# ES_Daisy_Pod_Rev3.net
KiCad netlist of a schematic drawn in EAGLE
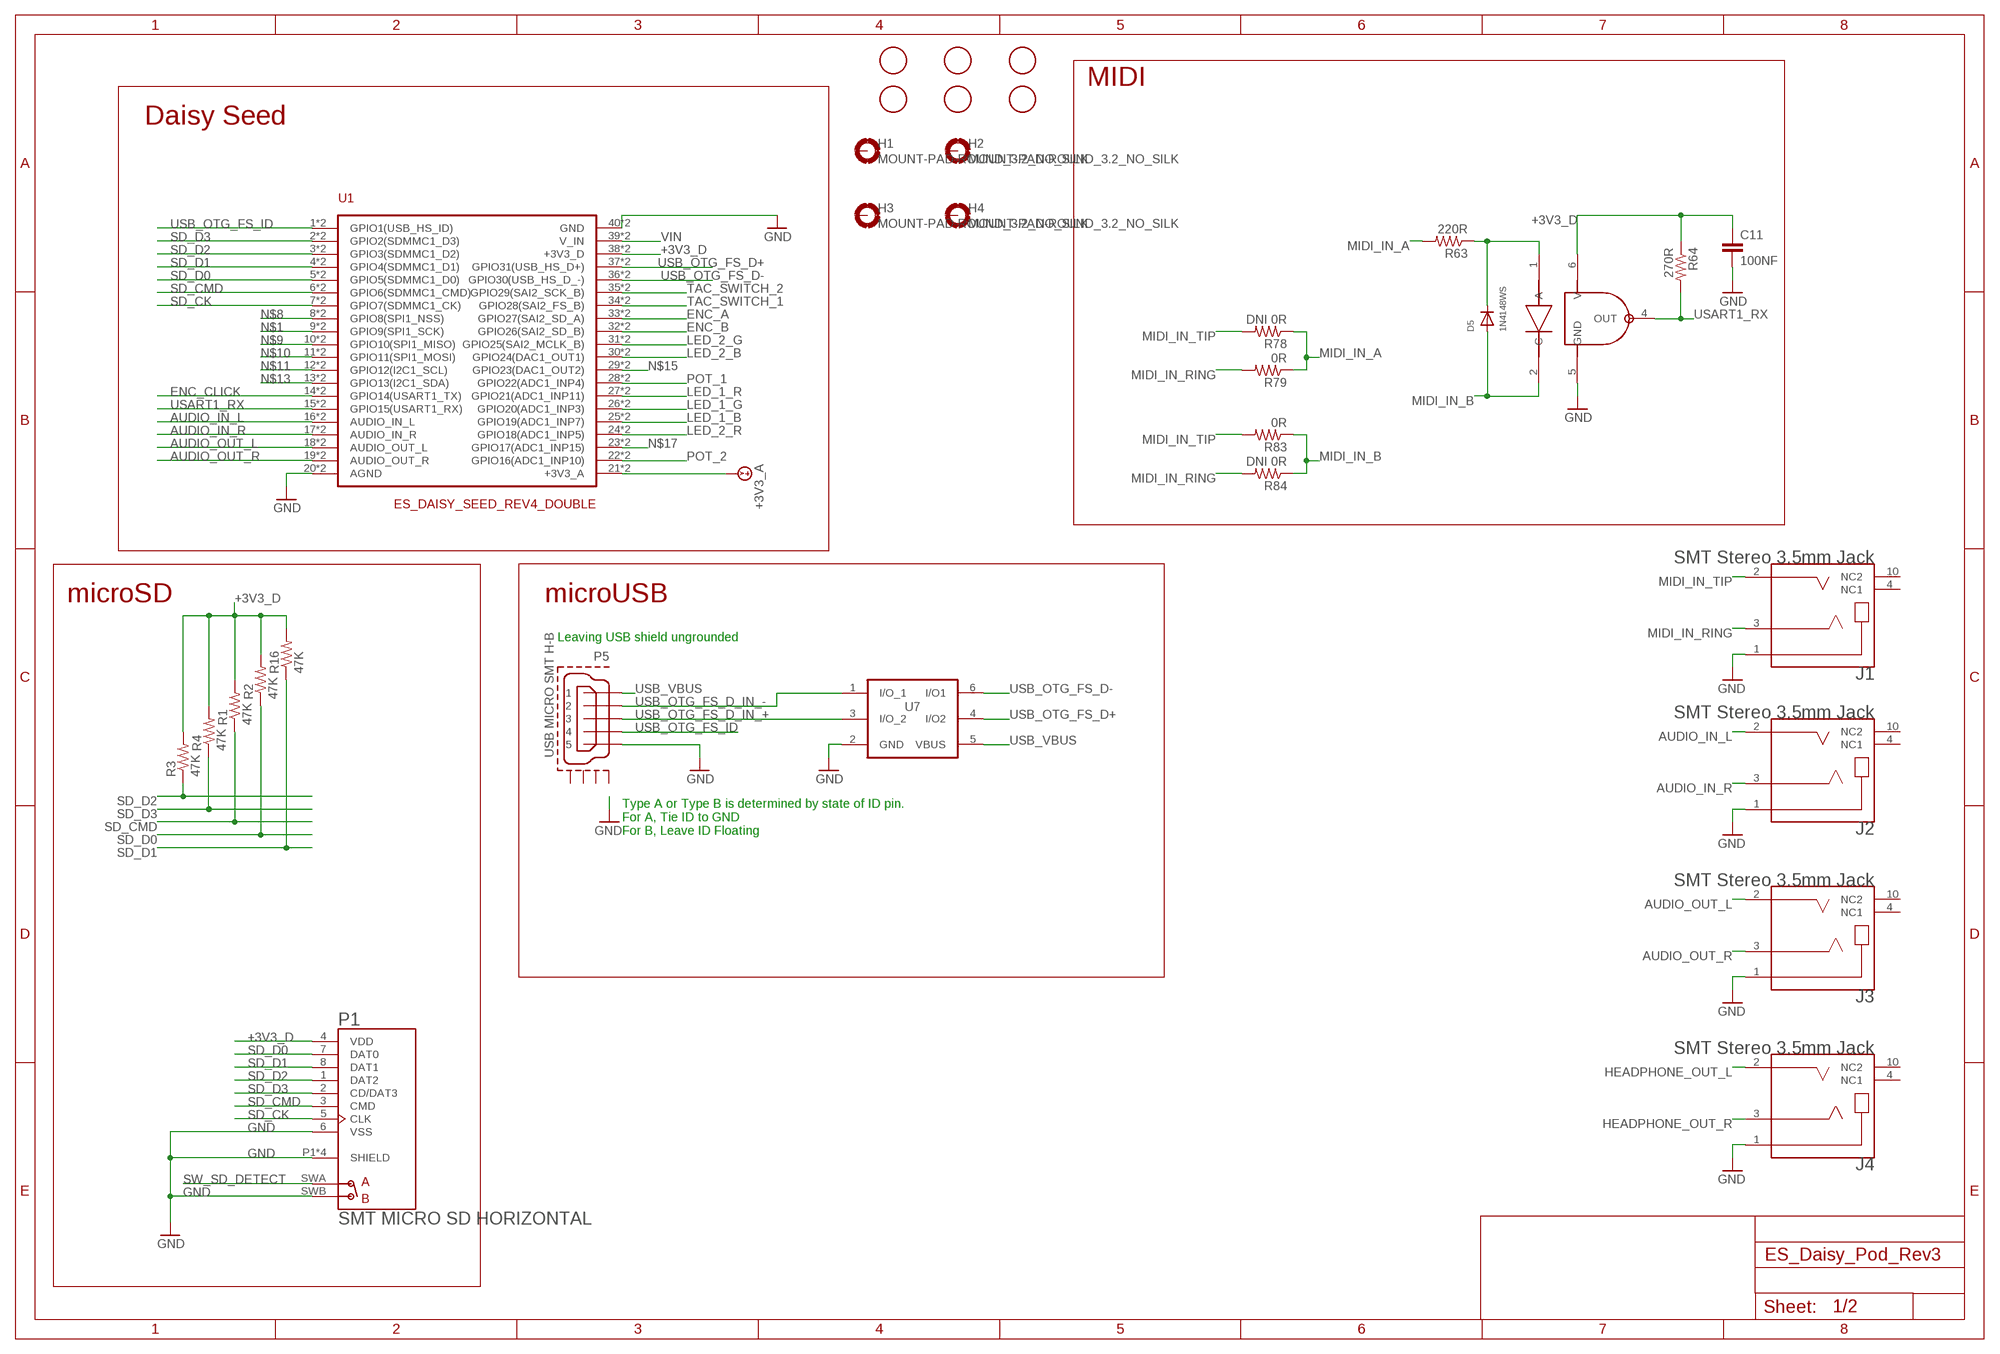
[diagram p0: schematic, sheet 1]
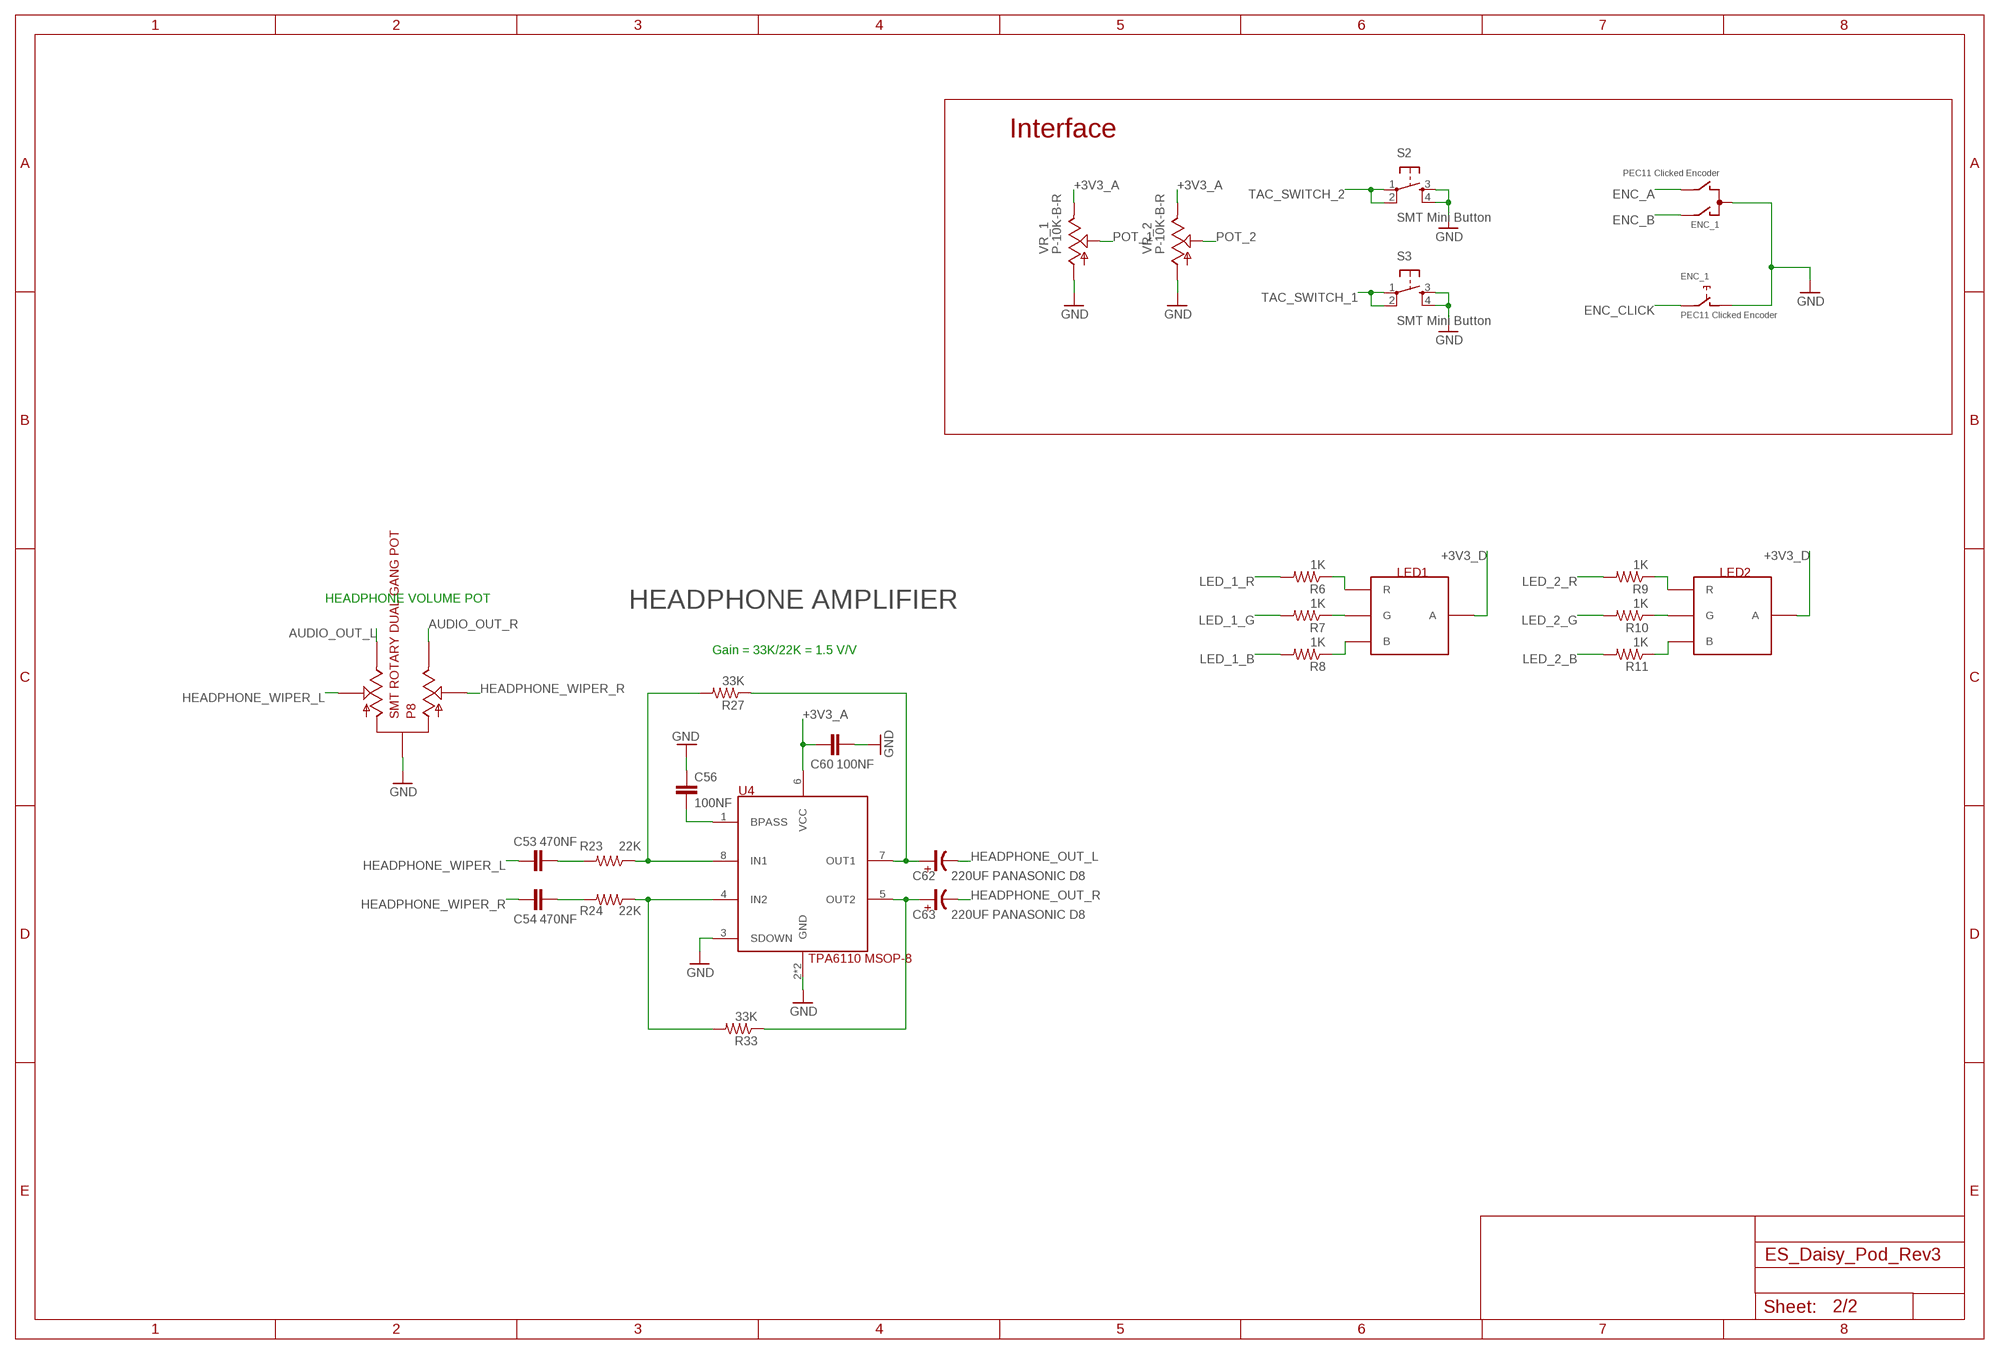
[diagram p1: schematic, sheet 2]

(export (version "E")
  (design (tool "Eeschema 10.0.6"))
  (components
    (comp (ref "C11")
      (value "100NF")
      (footprint "eagle-import:C0603")
      (libsource (lib "eagle-import") (part "C-EUC0603"))
    )
    (comp (ref "D5")
      (value "1N4148WS")
      (footprint "eagle-import:SOD-323F")
      (libsource (lib "eagle-import") (part "DIODE_SOD-323F"))
    )
    (comp (ref "FD1")
      (value "FIDUCIAL")
      (footprint "eagle-import:FIDUCIAL_1MM")
      (libsource (lib "eagle-import") (part "FIDUCIAL"))
    )
    (comp (ref "FD2")
      (value "FIDUCIAL")
      (footprint "eagle-import:FIDUCIAL_1MM")
      (libsource (lib "eagle-import") (part "FIDUCIAL"))
    )
    (comp (ref "FD3")
      (value "FIDUCIAL")
      (footprint "eagle-import:FIDUCIAL_1MM")
      (libsource (lib "eagle-import") (part "FIDUCIAL"))
    )
    (comp (ref "FD4")
      (value "FIDUCIAL")
      (footprint "eagle-import:FIDUCIAL_1MM")
      (libsource (lib "eagle-import") (part "FIDUCIAL"))
    )
    (comp (ref "FD5")
      (value "FIDUCIAL")
      (footprint "eagle-import:FIDUCIAL_1MM")
      (libsource (lib "eagle-import") (part "FIDUCIAL"))
    )
    (comp (ref "FD6")
      (value "FIDUCIAL")
      (footprint "eagle-import:FIDUCIAL_1MM")
      (libsource (lib "eagle-import") (part "FIDUCIAL"))
    )
    (comp (ref "H1")
      (value "MOUNT-PAD-ROUND_3.2_NO_SILK")
      (footprint "eagle-import:32-PAD_NO_SILK")
      (libsource (lib "eagle-import") (part "MOUNT-PAD-ROUND_3.2_NO_SILK"))
    )
    (comp (ref "H2")
      (value "MOUNT-PAD-ROUND_3.2_NO_SILK")
      (footprint "eagle-import:32-PAD_NO_SILK")
      (libsource (lib "eagle-import") (part "MOUNT-PAD-ROUND_3.2_NO_SILK"))
    )
    (comp (ref "H3")
      (value "MOUNT-PAD-ROUND_3.2_NO_SILK")
      (footprint "eagle-import:32-PAD_NO_SILK")
      (libsource (lib "eagle-import") (part "MOUNT-PAD-ROUND_3.2_NO_SILK"))
    )
    (comp (ref "H4")
      (value "MOUNT-PAD-ROUND_3.2_NO_SILK")
      (footprint "eagle-import:32-PAD_NO_SILK")
      (libsource (lib "eagle-import") (part "MOUNT-PAD-ROUND_3.2_NO_SILK"))
    )
    (comp (ref "J1")
      (value "SMT Stereo 3.5mm Jack")
      (footprint "eagle-import:CUI_SJ2-35863B1-SMT-TR")
      (fields (field (name "MF") "CUI Inc.") (field (name "MP") "SJ2-35863B1-SMT-TR"))
      (libsource (lib "eagle-import") (part "SJ2_TRS_JACK"))
    )
    (comp (ref "J2")
      (value "SMT Stereo 3.5mm Jack")
      (footprint "eagle-import:CUI_SJ2-35863B1-SMT-TR")
      (fields (field (name "MF") "CUI Inc.") (field (name "MP") "SJ2-35863B1-SMT-TR"))
      (libsource (lib "eagle-import") (part "SJ2_TRS_JACK"))
    )
    (comp (ref "J3")
      (value "SMT Stereo 3.5mm Jack")
      (footprint "eagle-import:CUI_SJ2-35863B1-SMT-TR")
      (fields (field (name "MF") "CUI Inc.") (field (name "MP") "SJ2-35863B1-SMT-TR"))
      (libsource (lib "eagle-import") (part "SJ2_TRS_JACK"))
    )
    (comp (ref "J4")
      (value "SMT Stereo 3.5mm Jack")
      (footprint "eagle-import:CUI_SJ2-35863B1-SMT-TR")
      (fields (field (name "MF") "CUI Inc.") (field (name "MP") "SJ2-35863B1-SMT-TR"))
      (libsource (lib "eagle-import") (part "SJ2_TRS_JACK"))
    )
    (comp (ref "P1")
      (value "SMT MICRO SD HORIZONTAL")
      (footprint "eagle-import:HRS_DM3AT-SF-PEJM5")
      (fields (field (name "MF") "Hirose") (field (name "MP") "DM3AT-SF-PEJM5"))
      (libsource (lib "eagle-import") (part "MICRO_SD_RIGHT_ANGLE"))
    )
    (comp (ref "P5")
      (value "USB MICRO SMT H-B")
      (footprint "eagle-import:47589-0001_CUT")
      (libsource (lib "eagle-import") (part "USB_MICRO_AB_CUT"))
    )
    (comp (ref "R1")
      (value "47K")
      (footprint "eagle-import:R0603")
      (libsource (lib "eagle-import") (part "R-US_R0603"))
    )
    (comp (ref "R2")
      (value "47K")
      (footprint "eagle-import:R0603")
      (libsource (lib "eagle-import") (part "R-US_R0603"))
    )
    (comp (ref "R3")
      (value "47K")
      (footprint "eagle-import:R0603")
      (libsource (lib "eagle-import") (part "R-US_R0603"))
    )
    (comp (ref "R4")
      (value "47K")
      (footprint "eagle-import:R0603")
      (libsource (lib "eagle-import") (part "R-US_R0603"))
    )
    (comp (ref "R16")
      (value "47K")
      (footprint "eagle-import:R0603")
      (libsource (lib "eagle-import") (part "R-US_R0603"))
    )
    (comp (ref "R63")
      (value "220R")
      (footprint "eagle-import:R0603")
      (libsource (lib "eagle-import") (part "R-US_R0603"))
    )
    (comp (ref "R64")
      (value "270R")
      (footprint "eagle-import:R0603")
      (libsource (lib "eagle-import") (part "R-US_R0603"))
    )
    (comp (ref "R78")
      (value "DNI 0R")
      (footprint "eagle-import:R0603")
      (libsource (lib "eagle-import") (part "R-US_R0603"))
    )
    (comp (ref "R79")
      (value "0R")
      (footprint "eagle-import:R0603")
      (libsource (lib "eagle-import") (part "R-US_R0603"))
    )
    (comp (ref "R83")
      (value "0R")
      (footprint "eagle-import:R0603")
      (libsource (lib "eagle-import") (part "R-US_R0603"))
    )
    (comp (ref "R84")
      (value "DNI 0R")
      (footprint "eagle-import:R0603")
      (libsource (lib "eagle-import") (part "R-US_R0603"))
    )
    (comp (ref "U1")
      (value "ES_DAISY_SEED_REV4_DOUBLE")
      (footprint "eagle-import:ES_DAISY_SEED_DOUBLE")
      (libsource (lib "eagle-import") (part "ES_DAISY_SEED_REV4_DOUBLE"))
    )
    (comp (ref "U7")
      (value "USBLC6 TVS SOT-23-6")
      (footprint "eagle-import:SOT-23-6L")
      (fields (field (name "MPN") "USBLC6-2SC6"))
      (libsource (lib "eagle-import") (part "USBLC6-2SC6"))
    )
    (comp (ref "U15")
      (value "H11L1SR2M")
      (footprint "eagle-import:DIL06_GULLWING")
      (libsource (lib "eagle-import") (part "OPTOISOLATOR_H11L1M"))
    )
    (comp (ref "C53")
      (value "470NF")
      (footprint "eagle-import:C0603")
      (libsource (lib "eagle-import") (part "C-EUC0603"))
    )
    (comp (ref "C54")
      (value "470NF")
      (footprint "eagle-import:C0603")
      (libsource (lib "eagle-import") (part "C-EUC0603"))
    )
    (comp (ref "C56")
      (value "100NF")
      (footprint "eagle-import:C0603")
      (libsource (lib "eagle-import") (part "C-EUC0603"))
    )
    (comp (ref "C60")
      (value "100NF")
      (footprint "eagle-import:C0603")
      (libsource (lib "eagle-import") (part "C-EUC0603"))
    )
    (comp (ref "C62")
      (value "220UF PANASONIC D8")
      (footprint "eagle-import:PANASONIC_D")
      (libsource (lib "eagle-import") (part "C-EU-POL_D"))
    )
    (comp (ref "C63")
      (value "220UF PANASONIC D8")
      (footprint "eagle-import:PANASONIC_D")
      (libsource (lib "eagle-import") (part "C-EU-POL_D"))
    )
    (comp (ref "ENC_1")
      (value "PEC11 Clicked Encoder")
      (footprint "eagle-import:PEC11_SILK")
      (libsource (lib "eagle-import") (part "ENCODERSILK_CLICK_"))
    )
    (comp (ref "LED1")
      (value "RGB LED SMT PLCC4")
      (footprint "eagle-import:P-LCC-4-3")
      (fields (field (name "MPN") "CLVBA-FKA-CC1F1L1BB7R3R3"))
      (libsource (lib "eagle-import") (part "LED_RGB_SMT"))
    )
    (comp (ref "LED2")
      (value "RGB LED SMT PLCC4")
      (footprint "eagle-import:P-LCC-4-3")
      (fields (field (name "MPN") "CLVBA-FKA-CC1F1L1BB7R3R3"))
      (libsource (lib "eagle-import") (part "LED_RGB_SMT"))
    )
    (comp (ref "P8")
      (value "SMT ROTARY DUAL GANG POT")
      (footprint "eagle-import:RK10J12R0A0B")
      (libsource (lib "eagle-import") (part "ROTARY_POT"))
    )
    (comp (ref "R6")
      (value "1K")
      (footprint "eagle-import:R0603")
      (libsource (lib "eagle-import") (part "R-US_R0603"))
    )
    (comp (ref "R7")
      (value "1K")
      (footprint "eagle-import:R0603")
      (libsource (lib "eagle-import") (part "R-US_R0603"))
    )
    (comp (ref "R8")
      (value "1K")
      (footprint "eagle-import:R0603")
      (libsource (lib "eagle-import") (part "R-US_R0603"))
    )
    (comp (ref "R9")
      (value "1K")
      (footprint "eagle-import:R0603")
      (libsource (lib "eagle-import") (part "R-US_R0603"))
    )
    (comp (ref "R10")
      (value "1K")
      (footprint "eagle-import:R0603")
      (libsource (lib "eagle-import") (part "R-US_R0603"))
    )
    (comp (ref "R11")
      (value "1K")
      (footprint "eagle-import:R0603")
      (libsource (lib "eagle-import") (part "R-US_R0603"))
    )
    (comp (ref "R23")
      (value "22K")
      (footprint "eagle-import:R0603")
      (libsource (lib "eagle-import") (part "R-US_R0603"))
    )
    (comp (ref "R24")
      (value "22K")
      (footprint "eagle-import:R0603")
      (libsource (lib "eagle-import") (part "R-US_R0603"))
    )
    (comp (ref "R27")
      (value "33K")
      (footprint "eagle-import:R0603")
      (libsource (lib "eagle-import") (part "R-US_R0603"))
    )
    (comp (ref "R33")
      (value "33K")
      (footprint "eagle-import:R0603")
      (libsource (lib "eagle-import") (part "R-US_R0603"))
    )
    (comp (ref "S2")
      (value "SMT Mini Button")
      (footprint "eagle-import:TL3301SPF160QJ")
      (fields (field (name "MPN") "TL3301SPF160QJ"))
      (libsource (lib "eagle-import") (part "TAC_SWITCH_SMT"))
    )
    (comp (ref "S3")
      (value "SMT Mini Button")
      (footprint "eagle-import:TL3301SPF160QJ")
      (fields (field (name "MPN") "TL3301SPF160QJ"))
      (libsource (lib "eagle-import") (part "TAC_SWITCH_SMT"))
    )
    (comp (ref "U4")
      (value "TPA6110 MSOP-8")
      (footprint "eagle-import:MSOP_8_PWRPAD")
      (libsource (lib "eagle-import") (part "TPA6110MSOP"))
    )
    (comp (ref "VR_1")
      (value "P-10K-B-R")
      (footprint "eagle-import:9MM_SNAP-IN_POT_SILK")
      (libsource (lib "eagle-import") (part "POT_9MM_SNAP-IN__"))
    )
    (comp (ref "VR_2")
      (value "P-10K-B-R")
      (footprint "eagle-import:9MM_SNAP-IN_POT_SILK")
      (libsource (lib "eagle-import") (part "POT_9MM_SNAP-IN__"))
    )
  )
  (nets
    (net (code "1") (name "+3V3_A") (class "Default")
      (node (ref "C60") (pin "2") (pinfunction "2_2") (pintype "passive"))
      (node (ref "U1") (pin "21") (pinfunction "+3V3_A_21") (pintype "bidirectional"))
      (node (ref "U1") (pin "B21") (pinfunction "+3V3_A_B21") (pintype "bidirectional"))
      (node (ref "U4") (pin "6") (pinfunction "VCC_6") (pintype "bidirectional"))
      (node (ref "VR_1") (pin "3") (pinfunction "3_3") (pintype "passive"))
      (node (ref "VR_2") (pin "3") (pinfunction "3_3") (pintype "passive"))
    )
    (net (code "2") (name "+3V3_D") (class "Default")
      (node (ref "C11") (pin "1") (pinfunction "1_1") (pintype "passive"))
      (node (ref "LED1") (pin "2") (pinfunction "A_2") (pintype "bidirectional"))
      (node (ref "LED2") (pin "2") (pinfunction "A_2") (pintype "bidirectional"))
      (node (ref "P1") (pin "4") (pinfunction "VDD_4") (pintype "power_in"))
      (node (ref "R1") (pin "2") (pinfunction "2_2") (pintype "passive"))
      (node (ref "R16") (pin "2") (pinfunction "2_2") (pintype "passive"))
      (node (ref "R2") (pin "2") (pinfunction "2_2") (pintype "passive"))
      (node (ref "R3") (pin "2") (pinfunction "2_2") (pintype "passive"))
      (node (ref "R4") (pin "2") (pinfunction "2_2") (pintype "passive"))
      (node (ref "R64") (pin "1") (pinfunction "1_1") (pintype "passive"))
      (node (ref "U1") (pin "38") (pinfunction "+3V3_D_38") (pintype "bidirectional"))
      (node (ref "U1") (pin "B38") (pinfunction "+3V3_D_B38") (pintype "bidirectional"))
      (node (ref "U15") (pin "6") (pinfunction "V_6") (pintype "bidirectional"))
    )
    (net (code "3") (name "AUDIO_IN_L") (class "Default")
      (node (ref "J2") (pin "2") (pinfunction "TIP_2") (pintype "passive"))
      (node (ref "U1") (pin "16") (pinfunction "AUDIO_IN_L_16") (pintype "bidirectional"))
      (node (ref "U1") (pin "B16") (pinfunction "AUDIO_IN_L_B16") (pintype "bidirectional"))
    )
    (net (code "4") (name "AUDIO_IN_R") (class "Default")
      (node (ref "J2") (pin "3") (pinfunction "RING_3") (pintype "passive"))
      (node (ref "U1") (pin "17") (pinfunction "AUDIO_IN_R_17") (pintype "bidirectional"))
      (node (ref "U1") (pin "B17") (pinfunction "AUDIO_IN_R_B17") (pintype "bidirectional"))
    )
    (net (code "5") (name "AUDIO_OUT_L") (class "Default")
      (node (ref "J3") (pin "2") (pinfunction "TIP_2") (pintype "passive"))
      (node (ref "P8") (pin "P$5") (pinfunction "P$5_P$5") (pintype "bidirectional"))
      (node (ref "U1") (pin "18") (pinfunction "AUDIO_OUT_L_18") (pintype "bidirectional"))
      (node (ref "U1") (pin "B18") (pinfunction "AUDIO_OUT_L_B18") (pintype "bidirectional"))
    )
    (net (code "6") (name "AUDIO_OUT_R") (class "Default")
      (node (ref "J3") (pin "3") (pinfunction "RING_3") (pintype "passive"))
      (node (ref "P8") (pin "P$4") (pinfunction "P$4_P$4") (pintype "bidirectional"))
      (node (ref "U1") (pin "19") (pinfunction "AUDIO_OUT_R_19") (pintype "bidirectional"))
      (node (ref "U1") (pin "B19") (pinfunction "AUDIO_OUT_R_B19") (pintype "bidirectional"))
    )
    (net (code "7") (name "ENC_A") (class "Default")
      (node (ref "ENC_1") (pin "B") (pinfunction "B_B") (pintype "passive"))
      (node (ref "U1") (pin "33") (pinfunction "GPIO27(SAI2_SD_A)_33") (pintype "bidirectional"))
      (node (ref "U1") (pin "B33") (pinfunction "GPIO27(SAI2_SD_A)_B33") (pintype "bidirectional"))
    )
    (net (code "8") (name "ENC_B") (class "Default")
      (node (ref "ENC_1") (pin "A") (pinfunction "A_A") (pintype "passive"))
      (node (ref "U1") (pin "32") (pinfunction "GPIO26(SAI2_SD_B)_32") (pintype "bidirectional"))
      (node (ref "U1") (pin "B32") (pinfunction "GPIO26(SAI2_SD_B)_B32") (pintype "bidirectional"))
    )
    (net (code "9") (name "ENC_CLICK") (class "Default")
      (node (ref "ENC_1") (pin "E") (pinfunction "2_E") (pintype "passive"))
      (node (ref "U1") (pin "14") (pinfunction "GPIO14(USART1_TX)_14") (pintype "bidirectional"))
      (node (ref "U1") (pin "B14") (pinfunction "GPIO14(USART1_TX)_B14") (pintype "bidirectional"))
    )
    (net (code "10") (name "GND") (class "Default")
      (node (ref "C11") (pin "2") (pinfunction "2_2") (pintype "passive"))
      (node (ref "C56") (pin "1") (pinfunction "1_1") (pintype "passive"))
      (node (ref "C60") (pin "1") (pinfunction "1_1") (pintype "passive"))
      (node (ref "ENC_1") (pin "C") (pinfunction "C_C") (pintype "passive"))
      (node (ref "ENC_1") (pin "D") (pinfunction "1_D") (pintype "passive"))
      (node (ref "J1") (pin "1") (pinfunction "SLEEVE_1") (pintype "passive"))
      (node (ref "J2") (pin "1") (pinfunction "SLEEVE_1") (pintype "passive"))
      (node (ref "J3") (pin "1") (pinfunction "SLEEVE_1") (pintype "passive"))
      (node (ref "J4") (pin "1") (pinfunction "SLEEVE_1") (pintype "passive"))
      (node (ref "P1") (pin "6") (pinfunction "VSS_6") (pintype "power_in"))
      (node (ref "P1") (pin "P1") (pinfunction "SHIELD_P1") (pintype "passive"))
      (node (ref "P1") (pin "P2") (pinfunction "SHIELD_P2") (pintype "passive"))
      (node (ref "P1") (pin "P3") (pinfunction "SHIELD_P3") (pintype "passive"))
      (node (ref "P1") (pin "P4") (pinfunction "SHIELD_P4") (pintype "passive"))
      (node (ref "P1") (pin "SWB") (pinfunction "B_SWB") (pintype "bidirectional"))
      (node (ref "P5") (pin "5") (pinfunction "5_5") (pintype "input"))
      (node (ref "P8") (pin "P$1") (pinfunction "P$1_P$1") (pintype "bidirectional"))
      (node (ref "S2") (pin "3") (pinfunction "3_3") (pintype "passive"))
      (node (ref "S2") (pin "4") (pinfunction "4_4") (pintype "passive"))
      (node (ref "S3") (pin "3") (pinfunction "3_3") (pintype "passive"))
      (node (ref "S3") (pin "4") (pinfunction "4_4") (pintype "passive"))
      (node (ref "U1") (pin "20") (pinfunction "AGND_20") (pintype "bidirectional"))
      (node (ref "U1") (pin "40") (pinfunction "GND_40") (pintype "bidirectional"))
      (node (ref "U1") (pin "B20") (pinfunction "AGND_B20") (pintype "bidirectional"))
      (node (ref "U1") (pin "B40") (pinfunction "GND_B40") (pintype "bidirectional"))
      (node (ref "U15") (pin "5") (pinfunction "GND_5") (pintype "bidirectional"))
      (node (ref "U4") (pin "2") (pinfunction "GND_2") (pintype "bidirectional"))
      (node (ref "U4") (pin "3") (pinfunction "SDOWN_3") (pintype "bidirectional"))
      (node (ref "U4") (pin "9") (pinfunction "GND_9") (pintype "bidirectional"))
      (node (ref "U7") (pin "2") (pinfunction "GND_2") (pintype "bidirectional"))
      (node (ref "VR_1") (pin "1") (pinfunction "1_1") (pintype "passive"))
      (node (ref "VR_2") (pin "1") (pinfunction "1_1") (pintype "passive"))
    )
    (net (code "11") (name "HEADPHONE_OUT_L") (class "Default")
      (node (ref "C62") (pin "-") (pinfunction "NEG_-") (pintype "passive"))
      (node (ref "J4") (pin "2") (pinfunction "TIP_2") (pintype "passive"))
    )
    (net (code "12") (name "HEADPHONE_OUT_R") (class "Default")
      (node (ref "C63") (pin "-") (pinfunction "NEG_-") (pintype "passive"))
      (node (ref "J4") (pin "3") (pinfunction "RING_3") (pintype "passive"))
    )
    (net (code "13") (name "HEADPHONE_WIPER_L") (class "Default")
      (node (ref "C53") (pin "1") (pinfunction "1_1") (pintype "passive"))
      (node (ref "P8") (pin "P$2") (pinfunction "P$2_P$2") (pintype "bidirectional"))
    )
    (net (code "14") (name "HEADPHONE_WIPER_R") (class "Default")
      (node (ref "C54") (pin "1") (pinfunction "1_1") (pintype "passive"))
      (node (ref "P8") (pin "P$3") (pinfunction "P$3_P$3") (pintype "bidirectional"))
    )
    (net (code "15") (name "LED_1_B") (class "Default")
      (node (ref "R8") (pin "2") (pinfunction "2_2") (pintype "passive"))
      (node (ref "U1") (pin "25") (pinfunction "GPIO19(ADC1_INP7)_25") (pintype "bidirectional"))
      (node (ref "U1") (pin "B25") (pinfunction "GPIO19(ADC1_INP7)_B25") (pintype "bidirectional"))
    )
    (net (code "16") (name "LED_1_G") (class "Default")
      (node (ref "R7") (pin "2") (pinfunction "2_2") (pintype "passive"))
      (node (ref "U1") (pin "26") (pinfunction "GPIO20(ADC1_INP3)_26") (pintype "bidirectional"))
      (node (ref "U1") (pin "B26") (pinfunction "GPIO20(ADC1_INP3)_B26") (pintype "bidirectional"))
    )
    (net (code "17") (name "LED_1_R") (class "Default")
      (node (ref "R6") (pin "2") (pinfunction "2_2") (pintype "passive"))
      (node (ref "U1") (pin "27") (pinfunction "GPIO21(ADC1_INP11)_27") (pintype "bidirectional"))
      (node (ref "U1") (pin "B27") (pinfunction "GPIO21(ADC1_INP11)_B27") (pintype "bidirectional"))
    )
    (net (code "18") (name "LED_2_B") (class "Default")
      (node (ref "R11") (pin "2") (pinfunction "2_2") (pintype "passive"))
      (node (ref "U1") (pin "30") (pinfunction "GPIO24(DAC1_OUT1)_30") (pintype "bidirectional"))
      (node (ref "U1") (pin "B30") (pinfunction "GPIO24(DAC1_OUT1)_B30") (pintype "bidirectional"))
    )
    (net (code "19") (name "LED_2_G") (class "Default")
      (node (ref "R10") (pin "2") (pinfunction "2_2") (pintype "passive"))
      (node (ref "U1") (pin "31") (pinfunction "GPIO25(SAI2_MCLK_B)_31") (pintype "bidirectional"))
      (node (ref "U1") (pin "B31") (pinfunction "GPIO25(SAI2_MCLK_B)_B31") (pintype "bidirectional"))
    )
    (net (code "20") (name "LED_2_R") (class "Default")
      (node (ref "R9") (pin "2") (pinfunction "2_2") (pintype "passive"))
      (node (ref "U1") (pin "24") (pinfunction "GPIO18(ADC1_INP5)_24") (pintype "bidirectional"))
      (node (ref "U1") (pin "B24") (pinfunction "GPIO18(ADC1_INP5)_B24") (pintype "bidirectional"))
    )
    (net (code "21") (name "MIDI_IN_A") (class "Default")
      (node (ref "R63") (pin "2") (pinfunction "2_2") (pintype "passive"))
      (node (ref "R78") (pin "1") (pinfunction "1_1") (pintype "passive"))
      (node (ref "R79") (pin "1") (pinfunction "1_1") (pintype "passive"))
    )
    (net (code "22") (name "MIDI_IN_B") (class "Default")
      (node (ref "D5") (pin "A") (pinfunction "A_A") (pintype "passive"))
      (node (ref "R83") (pin "1") (pinfunction "1_1") (pintype "passive"))
      (node (ref "R84") (pin "1") (pinfunction "1_1") (pintype "passive"))
      (node (ref "U15") (pin "2") (pinfunction "C_2") (pintype "bidirectional"))
    )
    (net (code "23") (name "MIDI_IN_RING") (class "Default")
      (node (ref "J1") (pin "3") (pinfunction "RING_3") (pintype "passive"))
      (node (ref "R79") (pin "2") (pinfunction "2_2") (pintype "passive"))
      (node (ref "R84") (pin "2") (pinfunction "2_2") (pintype "passive"))
    )
    (net (code "24") (name "MIDI_IN_TIP") (class "Default")
      (node (ref "J1") (pin "2") (pinfunction "TIP_2") (pintype "passive"))
      (node (ref "R78") (pin "2") (pinfunction "2_2") (pintype "passive"))
      (node (ref "R83") (pin "2") (pinfunction "2_2") (pintype "passive"))
    )
    (net (code "25") (name "N$1") (class "Default")
      (node (ref "U1") (pin "9") (pinfunction "GPIO9(SPI1_SCK)_9") (pintype "bidirectional"))
      (node (ref "U1") (pin "B9") (pinfunction "GPIO9(SPI1_SCK)_B9") (pintype "bidirectional"))
    )
    (net (code "26") (name "N$8") (class "Default")
      (node (ref "U1") (pin "8") (pinfunction "GPIO8(SPI1_NSS)_8") (pintype "bidirectional"))
      (node (ref "U1") (pin "B8") (pinfunction "GPIO8(SPI1_NSS)_B8") (pintype "bidirectional"))
    )
    (net (code "27") (name "N$9") (class "Default")
      (node (ref "U1") (pin "10") (pinfunction "GPIO10(SPI1_MISO)_10") (pintype "bidirectional"))
      (node (ref "U1") (pin "B10") (pinfunction "GPIO10(SPI1_MISO)_B10") (pintype "bidirectional"))
    )
    (net (code "28") (name "N$10") (class "Default")
      (node (ref "U1") (pin "11") (pinfunction "GPIO11(SPI1_MOSI)_11") (pintype "bidirectional"))
      (node (ref "U1") (pin "B11") (pinfunction "GPIO11(SPI1_MOSI)_B11") (pintype "bidirectional"))
    )
    (net (code "29") (name "N$11") (class "Default")
      (node (ref "U1") (pin "12") (pinfunction "GPIO12(I2C1_SCL)_12") (pintype "bidirectional"))
      (node (ref "U1") (pin "B12") (pinfunction "GPIO12(I2C1_SCL)_B12") (pintype "bidirectional"))
    )
    (net (code "30") (name "N$13") (class "Default")
      (node (ref "U1") (pin "13") (pinfunction "GPIO13(I2C1_SDA)_13") (pintype "bidirectional"))
      (node (ref "U1") (pin "B13") (pinfunction "GPIO13(I2C1_SDA)_B13") (pintype "bidirectional"))
    )
    (net (code "31") (name "N$15") (class "Default")
      (node (ref "U1") (pin "29") (pinfunction "GPIO23(DAC1_OUT2)_29") (pintype "bidirectional"))
      (node (ref "U1") (pin "B29") (pinfunction "GPIO23(DAC1_OUT2)_B29") (pintype "bidirectional"))
    )
    (net (code "32") (name "N$17") (class "Default")
      (node (ref "U1") (pin "23") (pinfunction "GPIO17(ADC1_INP15)_23") (pintype "bidirectional"))
      (node (ref "U1") (pin "B23") (pinfunction "GPIO17(ADC1_INP15)_B23") (pintype "bidirectional"))
    )
    (net (code "33") (name "Net-(C53-Pad2)") (class "Default")
      (node (ref "C53") (pin "2") (pinfunction "2_2") (pintype "passive"))
      (node (ref "R23") (pin "2") (pinfunction "2_2") (pintype "passive"))
    )
    (net (code "34") (name "Net-(C54-Pad2)") (class "Default")
      (node (ref "C54") (pin "2") (pinfunction "2_2") (pintype "passive"))
      (node (ref "R24") (pin "2") (pinfunction "2_2") (pintype "passive"))
    )
    (net (code "35") (name "Net-(C62-POS)") (class "Default")
      (node (ref "C62") (pin "+") (pinfunction "POS_+") (pintype "passive"))
      (node (ref "R27") (pin "1") (pinfunction "1_1") (pintype "passive"))
      (node (ref "U4") (pin "7") (pinfunction "OUT1_7") (pintype "bidirectional"))
    )
    (net (code "36") (name "Net-(C63-POS)") (class "Default")
      (node (ref "C63") (pin "+") (pinfunction "POS_+") (pintype "passive"))
      (node (ref "R33") (pin "1") (pinfunction "1_1") (pintype "passive"))
      (node (ref "U4") (pin "5") (pinfunction "OUT2_5") (pintype "bidirectional"))
    )
    (net (code "37") (name "Net-(LED1-B)") (class "Default")
      (node (ref "LED1") (pin "3") (pinfunction "B_3") (pintype "bidirectional"))
      (node (ref "R8") (pin "1") (pinfunction "1_1") (pintype "passive"))
    )
    (net (code "38") (name "Net-(LED1-G)") (class "Default")
      (node (ref "LED1") (pin "4") (pinfunction "G_4") (pintype "bidirectional"))
      (node (ref "R7") (pin "1") (pinfunction "1_1") (pintype "passive"))
    )
    (net (code "39") (name "Net-(LED1-R)") (class "Default")
      (node (ref "LED1") (pin "1") (pinfunction "R_1") (pintype "bidirectional"))
      (node (ref "R6") (pin "1") (pinfunction "1_1") (pintype "passive"))
    )
    (net (code "40") (name "Net-(LED2-B)") (class "Default")
      (node (ref "LED2") (pin "3") (pinfunction "B_3") (pintype "bidirectional"))
      (node (ref "R11") (pin "1") (pinfunction "1_1") (pintype "passive"))
    )
    (net (code "41") (name "Net-(LED2-G)") (class "Default")
      (node (ref "LED2") (pin "4") (pinfunction "G_4") (pintype "bidirectional"))
      (node (ref "R10") (pin "1") (pinfunction "1_1") (pintype "passive"))
    )
    (net (code "42") (name "Net-(LED2-R)") (class "Default")
      (node (ref "LED2") (pin "1") (pinfunction "R_1") (pintype "bidirectional"))
      (node (ref "R9") (pin "1") (pinfunction "1_1") (pintype "passive"))
    )
    (net (code "43") (name "Net-(U4-BPASS)") (class "Default")
      (node (ref "C56") (pin "2") (pinfunction "2_2") (pintype "passive"))
      (node (ref "U4") (pin "1") (pinfunction "BPASS_1") (pintype "bidirectional"))
    )
    (net (code "44") (name "Net-(U4-IN1)") (class "Default")
      (node (ref "R23") (pin "1") (pinfunction "1_1") (pintype "passive"))
      (node (ref "R27") (pin "2") (pinfunction "2_2") (pintype "passive"))
      (node (ref "U4") (pin "8") (pinfunction "IN1_8") (pintype "bidirectional"))
    )
    (net (code "45") (name "Net-(U4-IN2)") (class "Default")
      (node (ref "R24") (pin "1") (pinfunction "1_1") (pintype "passive"))
      (node (ref "R33") (pin "2") (pinfunction "2_2") (pintype "passive"))
      (node (ref "U4") (pin "4") (pinfunction "IN2_4") (pintype "bidirectional"))
    )
    (net (code "46") (name "Net-(U15-A)") (class "Default")
      (node (ref "D5") (pin "C") (pinfunction "C_C") (pintype "passive"))
      (node (ref "R63") (pin "1") (pinfunction "1_1") (pintype "passive"))
      (node (ref "U15") (pin "1") (pinfunction "A_1") (pintype "bidirectional"))
    )
    (net (code "47") (name "POT_1") (class "Default")
      (node (ref "U1") (pin "28") (pinfunction "GPIO22(ADC1_INP4)_28") (pintype "bidirectional"))
      (node (ref "U1") (pin "B28") (pinfunction "GPIO22(ADC1_INP4)_B28") (pintype "bidirectional"))
      (node (ref "VR_1") (pin "2") (pinfunction "2_2") (pintype "passive"))
    )
    (net (code "48") (name "POT_2") (class "Default")
      (node (ref "U1") (pin "22") (pinfunction "GPIO16(ADC1_INP10)_22") (pintype "bidirectional"))
      (node (ref "U1") (pin "B22") (pinfunction "GPIO16(ADC1_INP10)_B22") (pintype "bidirectional"))
      (node (ref "VR_2") (pin "2") (pinfunction "2_2") (pintype "passive"))
    )
    (net (code "49") (name "SD_CK") (class "Default")
      (node (ref "P1") (pin "5") (pinfunction "CLK_5") (pintype "bidirectional"))
      (node (ref "U1") (pin "7") (pinfunction "GPIO7(SDMMC1_CK)_7") (pintype "bidirectional"))
      (node (ref "U1") (pin "B7") (pinfunction "GPIO7(SDMMC1_CK)_B7") (pintype "bidirectional"))
    )
    (net (code "50") (name "SD_CMD") (class "Default")
      (node (ref "P1") (pin "3") (pinfunction "CMD_3") (pintype "bidirectional"))
      (node (ref "R1") (pin "1") (pinfunction "1_1") (pintype "passive"))
      (node (ref "U1") (pin "6") (pinfunction "GPIO6(SDMMC1_CMD)_6") (pintype "bidirectional"))
      (node (ref "U1") (pin "B6") (pinfunction "GPIO6(SDMMC1_CMD)_B6") (pintype "bidirectional"))
    )
    (net (code "51") (name "SD_D0") (class "Default")
      (node (ref "P1") (pin "7") (pinfunction "DAT0_7") (pintype "bidirectional"))
      (node (ref "R2") (pin "1") (pinfunction "1_1") (pintype "passive"))
      (node (ref "U1") (pin "5") (pinfunction "GPIO5(SDMMC1_D0)_5") (pintype "bidirectional"))
      (node (ref "U1") (pin "B5") (pinfunction "GPIO5(SDMMC1_D0)_B5") (pintype "bidirectional"))
    )
    (net (code "52") (name "SD_D1") (class "Default")
      (node (ref "P1") (pin "8") (pinfunction "DAT1_8") (pintype "bidirectional"))
      (node (ref "R16") (pin "1") (pinfunction "1_1") (pintype "passive"))
      (node (ref "U1") (pin "4") (pinfunction "GPIO4(SDMMC1_D1)_4") (pintype "bidirectional"))
      (node (ref "U1") (pin "B4") (pinfunction "GPIO4(SDMMC1_D1)_B4") (pintype "bidirectional"))
    )
    (net (code "53") (name "SD_D2") (class "Default")
      (node (ref "P1") (pin "1") (pinfunction "DAT2_1") (pintype "bidirectional"))
      (node (ref "R3") (pin "1") (pinfunction "1_1") (pintype "passive"))
      (node (ref "U1") (pin "3") (pinfunction "GPIO3(SDMMC1_D2)_3") (pintype "bidirectional"))
      (node (ref "U1") (pin "B3") (pinfunction "GPIO3(SDMMC1_D2)_B3") (pintype "bidirectional"))
    )
    (net (code "54") (name "SD_D3") (class "Default")
      (node (ref "P1") (pin "2") (pinfunction "CD/DAT3_2") (pintype "bidirectional"))
      (node (ref "R4") (pin "1") (pinfunction "1_1") (pintype "passive"))
      (node (ref "U1") (pin "2") (pinfunction "GPIO2(SDMMC1_D3)_2") (pintype "bidirectional"))
      (node (ref "U1") (pin "B2") (pinfunction "GPIO2(SDMMC1_D3)_B2") (pintype "bidirectional"))
    )
    (net (code "55") (name "SW_SD_DETECT") (class "Default")
      (node (ref "P1") (pin "SWA") (pinfunction "A_SWA") (pintype "bidirectional"))
    )
    (net (code "56") (name "TAC_SWITCH_1") (class "Default")
      (node (ref "S3") (pin "1") (pinfunction "1_1") (pintype "passive"))
      (node (ref "S3") (pin "2") (pinfunction "2_2") (pintype "passive"))
      (node (ref "U1") (pin "34") (pinfunction "GPIO28(SAI2_FS_B)_34") (pintype "bidirectional"))
      (node (ref "U1") (pin "B34") (pinfunction "GPIO28(SAI2_FS_B)_B34") (pintype "bidirectional"))
    )
    (net (code "57") (name "TAC_SWITCH_2") (class "Default")
      (node (ref "S2") (pin "1") (pinfunction "1_1") (pintype "passive"))
      (node (ref "S2") (pin "2") (pinfunction "2_2") (pintype "passive"))
      (node (ref "U1") (pin "35") (pinfunction "GPIO29(SAI2_SCK_B)_35") (pintype "bidirectional"))
      (node (ref "U1") (pin "B35") (pinfunction "GPIO29(SAI2_SCK_B)_B35") (pintype "bidirectional"))
    )
    (net (code "58") (name "USART1_RX") (class "Default")
      (node (ref "R64") (pin "2") (pinfunction "2_2") (pintype "passive"))
      (node (ref "U1") (pin "15") (pinfunction "GPIO15(USART1_RX)_15") (pintype "bidirectional"))
      (node (ref "U1") (pin "B15") (pinfunction "GPIO15(USART1_RX)_B15") (pintype "bidirectional"))
      (node (ref "U15") (pin "4") (pinfunction "OUT_4") (pintype "bidirectional"))
    )
    (net (code "59") (name "USB_OTG_FS_D+") (class "Default")
      (node (ref "U1") (pin "37") (pinfunction "GPIO31(USB_HS_D+)_37") (pintype "bidirectional"))
      (node (ref "U1") (pin "B37") (pinfunction "GPIO31(USB_HS_D+)_B37") (pintype "bidirectional"))
      (node (ref "U7") (pin "4") (pinfunction "I/O2_4") (pintype "bidirectional"))
    )
    (net (code "60") (name "USB_OTG_FS_D-") (class "Default")
      (node (ref "U1") (pin "36") (pinfunction "GPIO30(USB_HS_D_-)_36") (pintype "bidirectional"))
      (node (ref "U1") (pin "B36") (pinfunction "GPIO30(USB_HS_D_-)_B36") (pintype "bidirectional"))
      (node (ref "U7") (pin "6") (pinfunction "I/O1_6") (pintype "bidirectional"))
    )
    (net (code "61") (name "USB_OTG_FS_D_IN_+") (class "Default")
      (node (ref "P5") (pin "3") (pinfunction "3_3") (pintype "input"))
      (node (ref "U7") (pin "3") (pinfunction "I/O_2_3") (pintype "bidirectional"))
    )
    (net (code "62") (name "USB_OTG_FS_D_IN_-") (class "Default")
      (node (ref "P5") (pin "2") (pinfunction "2_2") (pintype "input"))
      (node (ref "U7") (pin "1") (pinfunction "I/O_1_1") (pintype "bidirectional"))
    )
    (net (code "63") (name "USB_OTG_FS_ID") (class "Default")
      (node (ref "P5") (pin "4") (pinfunction "4_4") (pintype "input"))
      (node (ref "U1") (pin "1") (pinfunction "GPIO1(USB_HS_ID)_1") (pintype "bidirectional"))
      (node (ref "U1") (pin "B1") (pinfunction "GPIO1(USB_HS_ID)_B1") (pintype "bidirectional"))
    )
    (net (code "64") (name "USB_VBUS") (class "Default")
      (node (ref "P5") (pin "1") (pinfunction "1_1") (pintype "input"))
      (node (ref "U7") (pin "5") (pinfunction "VBUS_5") (pintype "bidirectional"))
    )
    (net (code "65") (name "VIN") (class "Default")
      (node (ref "U1") (pin "39") (pinfunction "V_IN_39") (pintype "bidirectional"))
      (node (ref "U1") (pin "B39") (pinfunction "V_IN_B39") (pintype "bidirectional"))
    )
    (net (code "66") (name "unconnected-(H1-MOUNT-PadB3,2)") (class "Default")
      (node (ref "H1") (pin "B3,2") (pinfunction "MOUNT_B3,2") (pintype "passive"))
    )
    (net (code "67") (name "unconnected-(H2-MOUNT-PadB3,2)") (class "Default")
      (node (ref "H2") (pin "B3,2") (pinfunction "MOUNT_B3,2") (pintype "passive"))
    )
    (net (code "68") (name "unconnected-(H3-MOUNT-PadB3,2)") (class "Default")
      (node (ref "H3") (pin "B3,2") (pinfunction "MOUNT_B3,2") (pintype "passive"))
    )
    (net (code "69") (name "unconnected-(H4-MOUNT-PadB3,2)") (class "Default")
      (node (ref "H4") (pin "B3,2") (pinfunction "MOUNT_B3,2") (pintype "passive"))
    )
    (net (code "70") (name "unconnected-(J1-NC1-Pad4)") (class "Default")
      (node (ref "J1") (pin "4") (pinfunction "NC1_4") (pintype "bidirectional"))
    )
    (net (code "71") (name "unconnected-(J1-NC2-Pad10)") (class "Default")
      (node (ref "J1") (pin "10") (pinfunction "NC2_10") (pintype "bidirectional"))
    )
    (net (code "72") (name "unconnected-(J2-NC1-Pad4)") (class "Default")
      (node (ref "J2") (pin "4") (pinfunction "NC1_4") (pintype "bidirectional"))
    )
    (net (code "73") (name "unconnected-(J2-NC2-Pad10)") (class "Default")
      (node (ref "J2") (pin "10") (pinfunction "NC2_10") (pintype "bidirectional"))
    )
    (net (code "74") (name "unconnected-(J3-NC1-Pad4)") (class "Default")
      (node (ref "J3") (pin "4") (pinfunction "NC1_4") (pintype "bidirectional"))
    )
    (net (code "75") (name "unconnected-(J3-NC2-Pad10)") (class "Default")
      (node (ref "J3") (pin "10") (pinfunction "NC2_10") (pintype "bidirectional"))
    )
    (net (code "76") (name "unconnected-(J4-NC1-Pad4)") (class "Default")
      (node (ref "J4") (pin "4") (pinfunction "NC1_4") (pintype "bidirectional"))
    )
    (net (code "77") (name "unconnected-(J4-NC2-Pad10)") (class "Default")
      (node (ref "J4") (pin "10") (pinfunction "NC2_10") (pintype "bidirectional"))
    )
    (net (code "78") (name "unconnected-(P5-GND1-PadCASING1)") (class "Default")
      (node (ref "P5") (pin "CASING1") (pinfunction "GND1_CASING1") (pintype "bidirectional"))
    )
    (net (code "79") (name "unconnected-(P5-GND2-PadCASING2)") (class "Default")
      (node (ref "P5") (pin "CASING2") (pinfunction "GND2_CASING2") (pintype "bidirectional"))
    )
    (net (code "80") (name "unconnected-(P5-GND3-PadCASING3)") (class "Default")
      (node (ref "P5") (pin "CASING3") (pinfunction "GND3_CASING3") (pintype "bidirectional"))
    )
    (net (code "81") (name "unconnected-(P5-GND4-PadCASING4)") (class "Default")
      (node (ref "P5") (pin "CASING4") (pinfunction "GND4_CASING4") (pintype "bidirectional"))
    )
  )
)
